# SCH_esp_micro_usb.net
KiCad netlist of a schematic drawn in EasyEDA
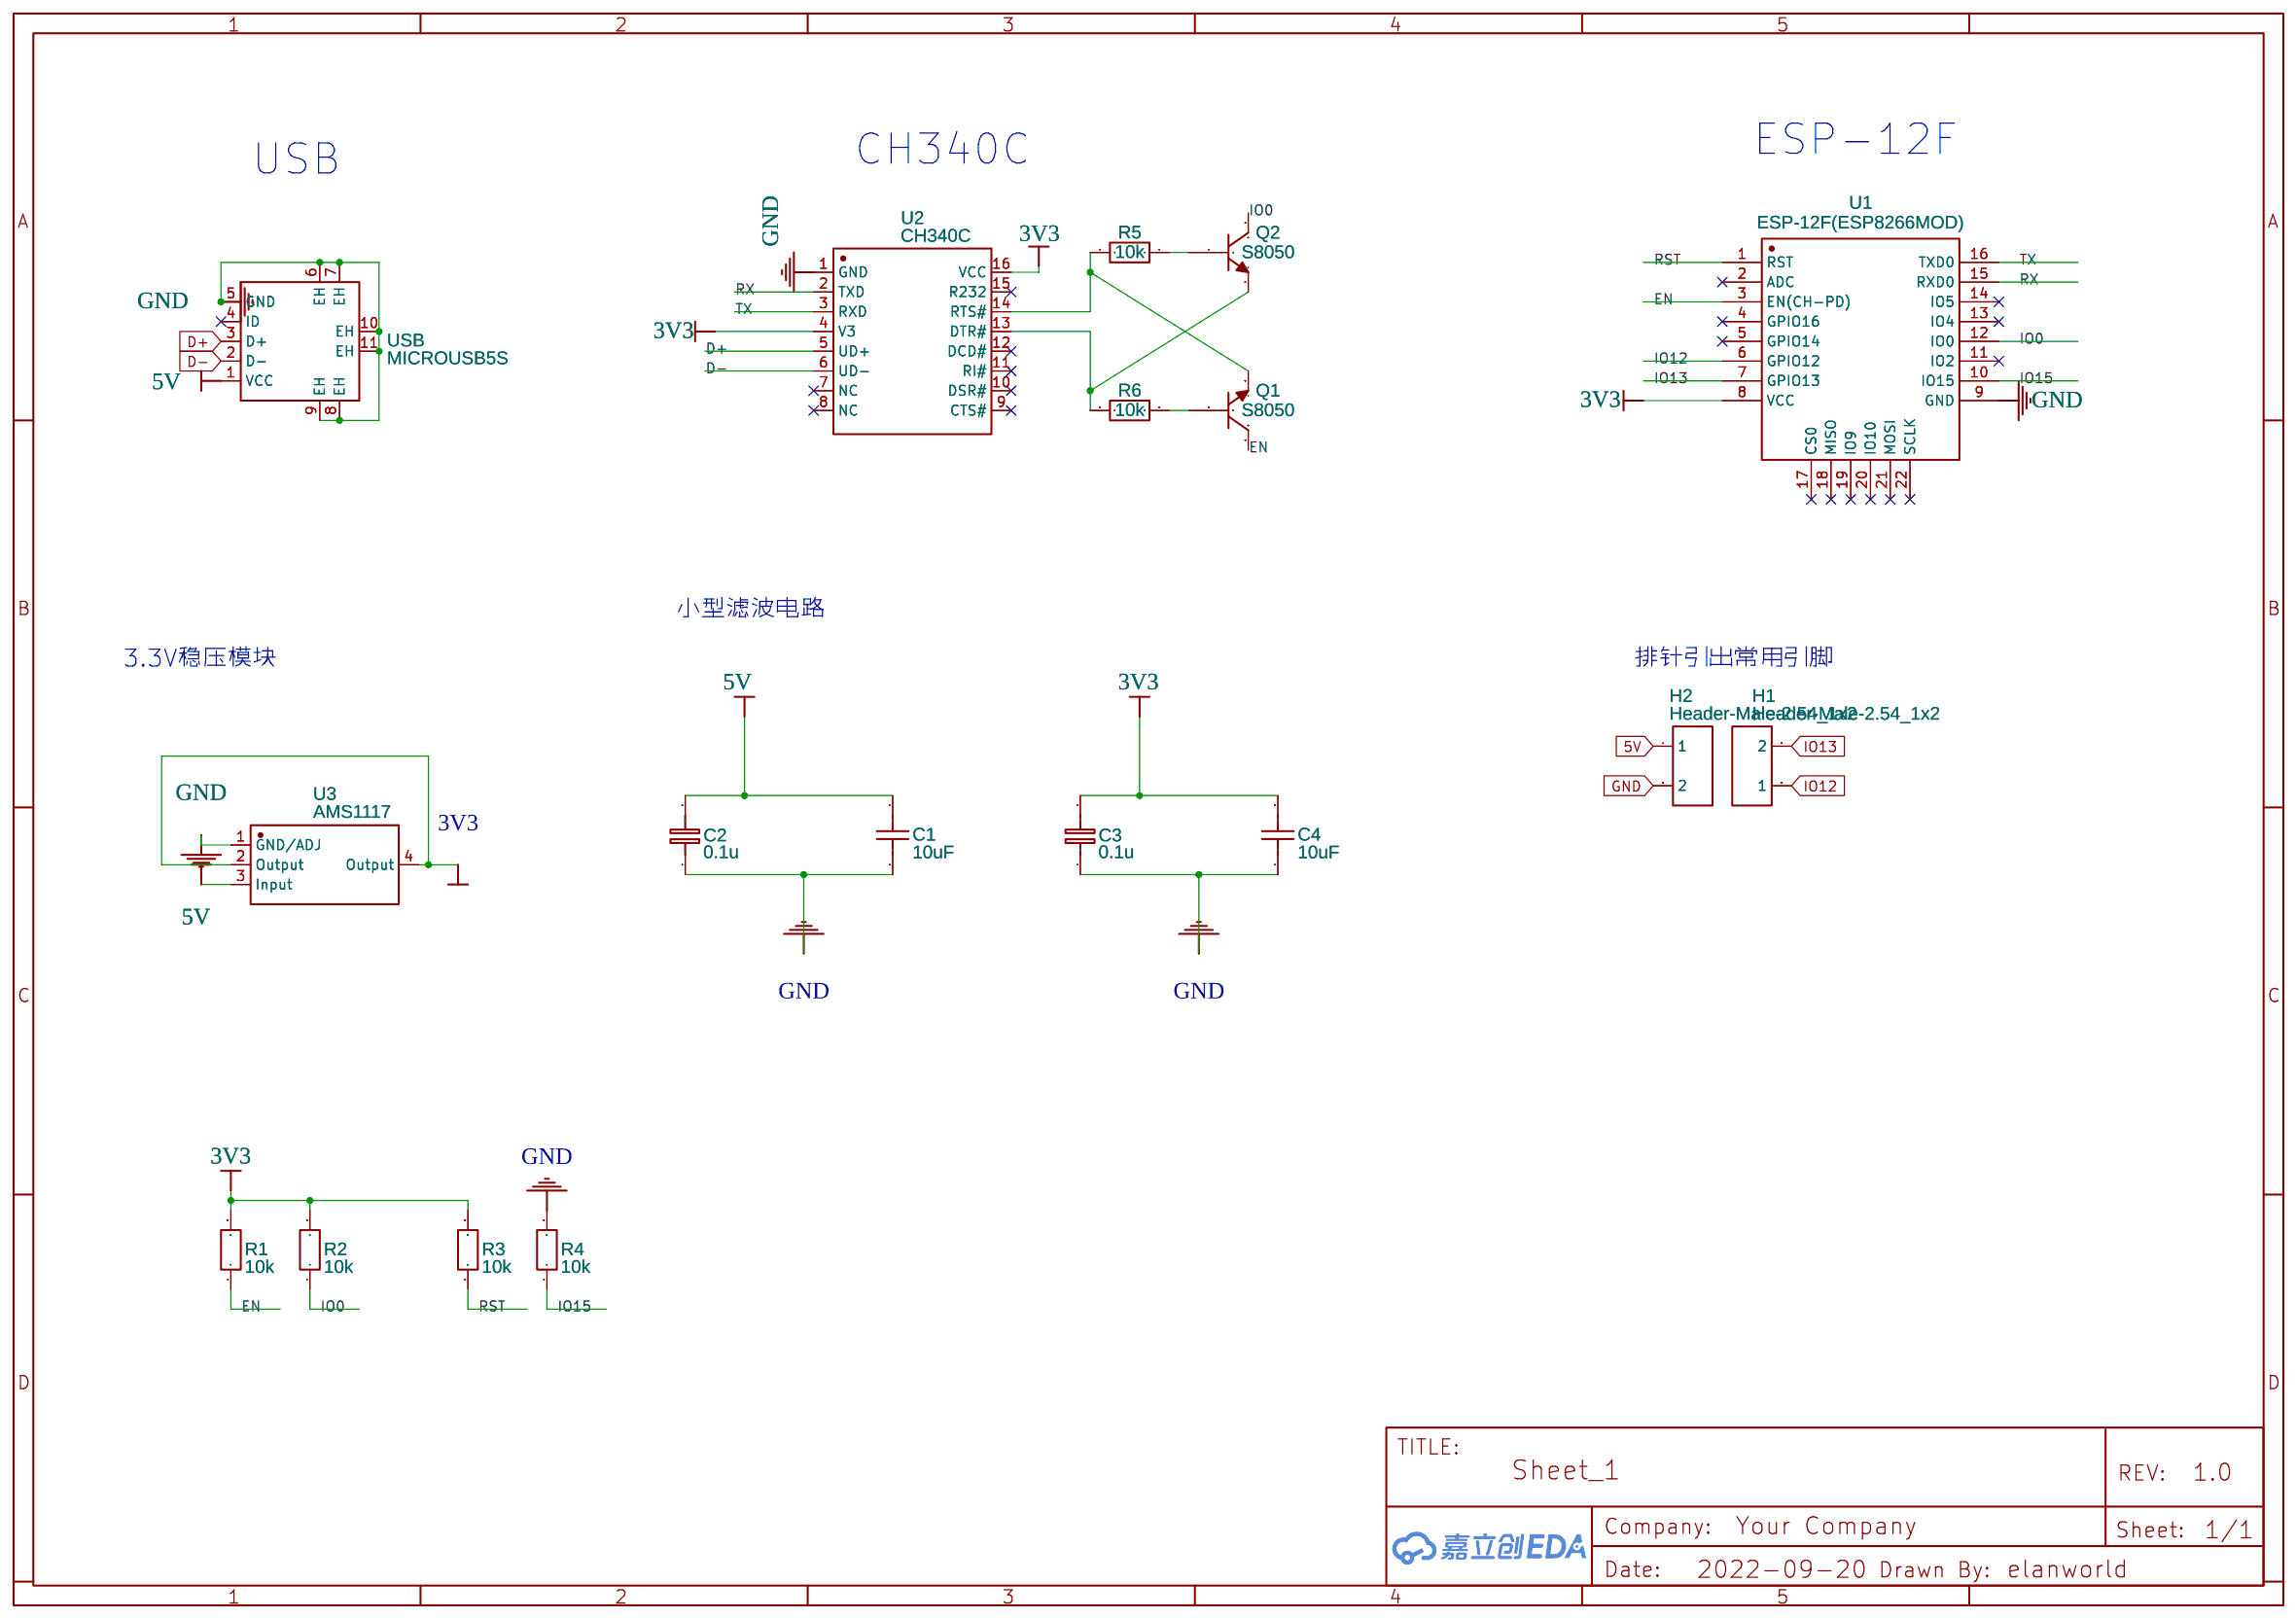
[diagram p0: schematic sheet]

(export (version "E")
  (design (tool "Eeschema 10.0.6"))
  (components
    (comp (ref "C1")
      (value "10uF")
      (fields
        (field (name "BOM_Manufacturer Part") "CL10A106MP8NNNC")
        (field (name "BOM_Supplier Part") "C85713")
      )
      (libsource (lib "") (part "CL10A106MP8NNNC"))
    )
    (comp (ref "C2")
      (value "0.1u")
      (fields (field (name "BOM_Supplier Part") "C1591"))
      (libsource (lib "") (part "C_0603_EU_1"))
    )
    (comp (ref "C3")
      (value "0.1u")
      (fields (field (name "BOM_Supplier Part") "C1591"))
      (libsource (lib "") (part "C_0603_EU"))
    )
    (comp (ref "C4")
      (value "10uF")
      (fields
        (field (name "BOM_Manufacturer Part") "CL10A106MP8NNNC")
        (field (name "BOM_Supplier Part") "C85713")
      )
      (libsource (lib "") (part "CL10A106MP8NNNC"))
    )
    (comp (ref "H1")
      (value "Header-Male-2.54_1x2")
      (fields (field (name "BOM_Manufacturer Part") "826629-2") (field (name "BOM_Supplier Part") "C86471"))
      (libsource (lib "") (part "Header-Male-2.54_1x2_1"))
    )
    (comp (ref "H2")
      (value "Header-Male-2.54_1x2")
      (fields (field (name "BOM_Manufacturer Part") "826629-2") (field (name "BOM_Supplier Part") "C86471"))
      (libsource (lib "") (part "Header-Male-2.54_1x2"))
    )
    (comp (ref "Q1")
      (value "S8050")
      (fields (field (name "BOM_Supplier Part") "C364312"))
      (libsource (lib "") (part "Unknown_615_-605"))
    )
    (comp (ref "Q2")
      (value "S8050")
      (fields (field (name "BOM_Supplier Part") "C364312"))
      (libsource (lib "") (part "Unknown_615_-685"))
    )
    (comp (ref "R1")
      (value "10k")
      (fields (field (name "BOM_Supplier Part") "C169103"))
      (libsource (lib "") (part "R_0603_EU"))
    )
    (comp (ref "R2")
      (value "10k")
      (fields (field (name "BOM_Supplier Part") "C169103"))
      (libsource (lib "") (part "R_0603_EU"))
    )
    (comp (ref "R3")
      (value "10k")
      (fields (field (name "BOM_Supplier Part") "C169103"))
      (libsource (lib "") (part "R_0603_EU"))
    )
    (comp (ref "R4")
      (value "10k")
      (fields (field (name "BOM_Supplier Part") "C169103"))
      (libsource (lib "") (part "R_0603_EU"))
    )
    (comp (ref "R5")
      (value "10k")
      (fields (field (name "BOM_Supplier Part") "C169103"))
      (libsource (lib "") (part "Res_0603(1/10W)_EU"))
    )
    (comp (ref "R6")
      (value "10k")
      (fields (field (name "BOM_Supplier Part") "C169103"))
      (libsource (lib "") (part "Res_0603(1/10W)_EU"))
    )
    (comp (ref "U1")
      (value "ESP-12F(ESP8266MOD)")
      (fields (field (name "BOM_Supplier Part") "C82891"))
      (libsource (lib "") (part "ESP-12F(ESP8266MOD)"))
    )
    (comp (ref "U2")
      (value "CH340C")
      (fields (field (name "BOM_Supplier Part") "C84681"))
      (libsource (lib "") (part "Unknown_455_-685"))
    )
    (comp (ref "U3")
      (value "AMS1117")
      (fields
        (field (name "BOM_Manufacturer Part") "AMS1117-3.3")
        (field (name "BOM_Supplier Part") "C369933")
      )
      (libsource (lib "") (part "AMS1117-3.3_C369933"))
    )
    (comp (ref "USB")
      (value "MICROUSB5S")
      (fields (field (name "BOM_Supplier Part") "C9900018063"))
      (libsource (lib "") (part "MICROUSB5S"))
    )
  )
  (nets
    (net (code "1") (name "/EN") (class "Default")
      (node (ref "Q1") (pin "3") (pinfunction "C_3") (pintype "unspecified"))
      (node (ref "R1") (pin "1") (pinfunction "1_1") (pintype "unspecified"))
      (node (ref "U1") (pin "3") (pinfunction "EN(CH-PD)_3") (pintype "unspecified"))
    )
    (net (code "2") (name "/IO0") (class "Default")
      (node (ref "Q2") (pin "3") (pinfunction "C_3") (pintype "unspecified"))
      (node (ref "R2") (pin "1") (pinfunction "1_1") (pintype "unspecified"))
      (node (ref "U1") (pin "12") (pinfunction "IO0_12") (pintype "unspecified"))
    )
    (net (code "3") (name "/IO15") (class "Default")
      (node (ref "R4") (pin "1") (pinfunction "1_1") (pintype "unspecified"))
      (node (ref "U1") (pin "10") (pinfunction "IO15_10") (pintype "unspecified"))
    )
    (net (code "4") (name "/RST") (class "Default")
      (node (ref "R3") (pin "1") (pinfunction "1_1") (pintype "unspecified"))
      (node (ref "U1") (pin "1") (pinfunction "RST_1") (pintype "unspecified"))
    )
    (net (code "5") (name "/RX") (class "Default")
      (node (ref "U1") (pin "15") (pinfunction "RXD0_15") (pintype "unspecified"))
      (node (ref "U2") (pin "2") (pinfunction "TXD_2") (pintype "unspecified"))
    )
    (net (code "6") (name "/TX") (class "Default")
      (node (ref "U1") (pin "16") (pinfunction "TXD0_16") (pintype "unspecified"))
      (node (ref "U2") (pin "3") (pinfunction "RXD_3") (pintype "unspecified"))
    )
    (net (code "7") (name "3V3") (class "Default")
      (node (ref "C3") (pin "2") (pinfunction "2_2") (pintype "unspecified"))
      (node (ref "C4") (pin "2") (pinfunction "2_2") (pintype "unspecified"))
      (node (ref "R1") (pin "2") (pinfunction "2_2") (pintype "unspecified"))
      (node (ref "R2") (pin "2") (pinfunction "2_2") (pintype "unspecified"))
      (node (ref "R3") (pin "2") (pinfunction "2_2") (pintype "unspecified"))
      (node (ref "U1") (pin "8") (pinfunction "VCC_8") (pintype "unspecified"))
      (node (ref "U2") (pin "16") (pinfunction "VCC_16") (pintype "unspecified"))
      (node (ref "U2") (pin "4") (pinfunction "V3_4") (pintype "unspecified"))
      (node (ref "U3") (pin "2") (pinfunction "Output_2") (pintype "unspecified"))
      (node (ref "U3") (pin "4") (pinfunction "Output_4") (pintype "unspecified"))
    )
    (net (code "8") (name "5V") (class "Default")
      (node (ref "C1") (pin "2") (pinfunction "2_2") (pintype "unspecified"))
      (node (ref "C2") (pin "2") (pinfunction "2_2") (pintype "unspecified"))
      (node (ref "H2") (pin "1") (pinfunction "1_1") (pintype "unspecified"))
      (node (ref "U3") (pin "3") (pinfunction "Input_3") (pintype "unspecified"))
      (node (ref "USB") (pin "1") (pinfunction "VCC_1") (pintype "input"))
    )
    (net (code "9") (name "D+") (class "Default")
      (node (ref "U2") (pin "5") (pinfunction "UD+_5") (pintype "unspecified"))
      (node (ref "USB") (pin "3") (pinfunction "D+_3") (pintype "input"))
    )
    (net (code "10") (name "D-") (class "Default")
      (node (ref "U2") (pin "6") (pinfunction "UD-_6") (pintype "unspecified"))
      (node (ref "USB") (pin "2") (pinfunction "D-_2") (pintype "input"))
    )
    (net (code "11") (name "GND") (class "Default")
      (node (ref "C1") (pin "1") (pinfunction "1_1") (pintype "unspecified"))
      (node (ref "C2") (pin "1") (pinfunction "1_1") (pintype "unspecified"))
      (node (ref "C3") (pin "1") (pinfunction "1_1") (pintype "unspecified"))
      (node (ref "C4") (pin "1") (pinfunction "1_1") (pintype "unspecified"))
      (node (ref "H2") (pin "2") (pinfunction "2_2") (pintype "unspecified"))
      (node (ref "R4") (pin "2") (pinfunction "2_2") (pintype "unspecified"))
      (node (ref "U1") (pin "9") (pinfunction "GND_9") (pintype "unspecified"))
      (node (ref "U2") (pin "1") (pinfunction "GND_1") (pintype "unspecified"))
      (node (ref "U3") (pin "1") (pinfunction "GND/ADJ_1") (pintype "unspecified"))
      (node (ref "USB") (pin "10") (pinfunction "EH_10") (pintype "unspecified"))
      (node (ref "USB") (pin "11") (pinfunction "EH_11") (pintype "unspecified"))
      (node (ref "USB") (pin "5") (pinfunction "GND_5") (pintype "input"))
      (node (ref "USB") (pin "6") (pinfunction "EH_6") (pintype "unspecified"))
      (node (ref "USB") (pin "7") (pinfunction "EH_7") (pintype "unspecified"))
      (node (ref "USB") (pin "8") (pinfunction "EH_8") (pintype "unspecified"))
      (node (ref "USB") (pin "9") (pinfunction "EH_9") (pintype "unspecified"))
    )
    (net (code "12") (name "IO12") (class "Default")
      (node (ref "H1") (pin "1") (pinfunction "1_1") (pintype "unspecified"))
      (node (ref "U1") (pin "6") (pinfunction "GPIO12_6") (pintype "unspecified"))
    )
    (net (code "13") (name "IO13") (class "Default")
      (node (ref "H1") (pin "2") (pinfunction "2_2") (pintype "unspecified"))
      (node (ref "U1") (pin "7") (pinfunction "GPIO13_7") (pintype "unspecified"))
    )
    (net (code "14") (name "Net-(Q1-B)") (class "Default")
      (node (ref "Q1") (pin "1") (pinfunction "B_1") (pintype "unspecified"))
      (node (ref "R6") (pin "1") (pinfunction "1_1") (pintype "unspecified"))
    )
    (net (code "15") (name "Net-(Q1-E)") (class "Default")
      (node (ref "Q1") (pin "2") (pinfunction "E_2") (pintype "unspecified"))
      (node (ref "R5") (pin "2") (pinfunction "2_2") (pintype "unspecified"))
      (node (ref "U2") (pin "14") (pinfunction "RTS#_14") (pintype "unspecified"))
    )
    (net (code "16") (name "Net-(Q2-B)") (class "Default")
      (node (ref "Q2") (pin "1") (pinfunction "B_1") (pintype "unspecified"))
      (node (ref "R5") (pin "1") (pinfunction "1_1") (pintype "unspecified"))
    )
    (net (code "17") (name "Net-(Q2-E)") (class "Default")
      (node (ref "Q2") (pin "2") (pinfunction "E_2") (pintype "unspecified"))
      (node (ref "R6") (pin "2") (pinfunction "2_2") (pintype "unspecified"))
      (node (ref "U2") (pin "13") (pinfunction "DTR#_13") (pintype "unspecified"))
    )
    (net (code "18") (name "unconnected-(U1-ADC-Pad2)") (class "Default")
      (node (ref "U1") (pin "2") (pinfunction "ADC_2") (pintype "unspecified+no_connect"))
    )
    (net (code "19") (name "unconnected-(U1-CS0-Pad17)") (class "Default")
      (node (ref "U1") (pin "17") (pinfunction "CS0_17") (pintype "unspecified+no_connect"))
    )
    (net (code "20") (name "unconnected-(U1-GPIO14-Pad5)") (class "Default")
      (node (ref "U1") (pin "5") (pinfunction "GPIO14_5") (pintype "unspecified+no_connect"))
    )
    (net (code "21") (name "unconnected-(U1-GPIO16-Pad4)") (class "Default")
      (node (ref "U1") (pin "4") (pinfunction "GPIO16_4") (pintype "unspecified+no_connect"))
    )
    (net (code "22") (name "unconnected-(U1-IO2-Pad11)") (class "Default")
      (node (ref "U1") (pin "11") (pinfunction "IO2_11") (pintype "unspecified+no_connect"))
    )
    (net (code "23") (name "unconnected-(U1-IO4-Pad13)") (class "Default")
      (node (ref "U1") (pin "13") (pinfunction "IO4_13") (pintype "unspecified+no_connect"))
    )
    (net (code "24") (name "unconnected-(U1-IO5-Pad14)") (class "Default")
      (node (ref "U1") (pin "14") (pinfunction "IO5_14") (pintype "unspecified+no_connect"))
    )
    (net (code "25") (name "unconnected-(U1-IO9-Pad19)") (class "Default")
      (node (ref "U1") (pin "19") (pinfunction "IO9_19") (pintype "unspecified+no_connect"))
    )
    (net (code "26") (name "unconnected-(U1-IO10-Pad20)") (class "Default")
      (node (ref "U1") (pin "20") (pinfunction "IO10_20") (pintype "unspecified+no_connect"))
    )
    (net (code "27") (name "unconnected-(U1-MISO-Pad18)") (class "Default")
      (node (ref "U1") (pin "18") (pinfunction "MISO_18") (pintype "unspecified+no_connect"))
    )
    (net (code "28") (name "unconnected-(U1-MOSI-Pad21)") (class "Default")
      (node (ref "U1") (pin "21") (pinfunction "MOSI_21") (pintype "unspecified+no_connect"))
    )
    (net (code "29") (name "unconnected-(U1-SCLK-Pad22)") (class "Default")
      (node (ref "U1") (pin "22") (pinfunction "SCLK_22") (pintype "unspecified+no_connect"))
    )
    (net (code "30") (name "unconnected-(U2-CTS#-Pad9)") (class "Default")
      (node (ref "U2") (pin "9") (pinfunction "CTS#_9") (pintype "unspecified+no_connect"))
    )
    (net (code "31") (name "unconnected-(U2-DCD#-Pad12)") (class "Default")
      (node (ref "U2") (pin "12") (pinfunction "DCD#_12") (pintype "unspecified+no_connect"))
    )
    (net (code "32") (name "unconnected-(U2-DSR#-Pad10)") (class "Default")
      (node (ref "U2") (pin "10") (pinfunction "DSR#_10") (pintype "unspecified+no_connect"))
    )
    (net (code "33") (name "unconnected-(U2-NC-Pad7)") (class "Default")
      (node (ref "U2") (pin "7") (pinfunction "NC_7") (pintype "unspecified+no_connect"))
    )
    (net (code "34") (name "unconnected-(U2-NC-Pad8)") (class "Default")
      (node (ref "U2") (pin "8") (pinfunction "NC_8") (pintype "unspecified+no_connect"))
    )
    (net (code "35") (name "unconnected-(U2-R232-Pad15)") (class "Default")
      (node (ref "U2") (pin "15") (pinfunction "R232_15") (pintype "unspecified+no_connect"))
    )
    (net (code "36") (name "unconnected-(U2-RI#-Pad11)") (class "Default")
      (node (ref "U2") (pin "11") (pinfunction "RI#_11") (pintype "unspecified+no_connect"))
    )
    (net (code "37") (name "unconnected-(USB-ID-Pad4)") (class "Default")
      (node (ref "USB") (pin "4") (pinfunction "ID_4") (pintype "input+no_connect"))
    )
  )
)
